# SCH_EasyEDA_EDA.net
KiCad netlist of a schematic drawn in EasyEDA
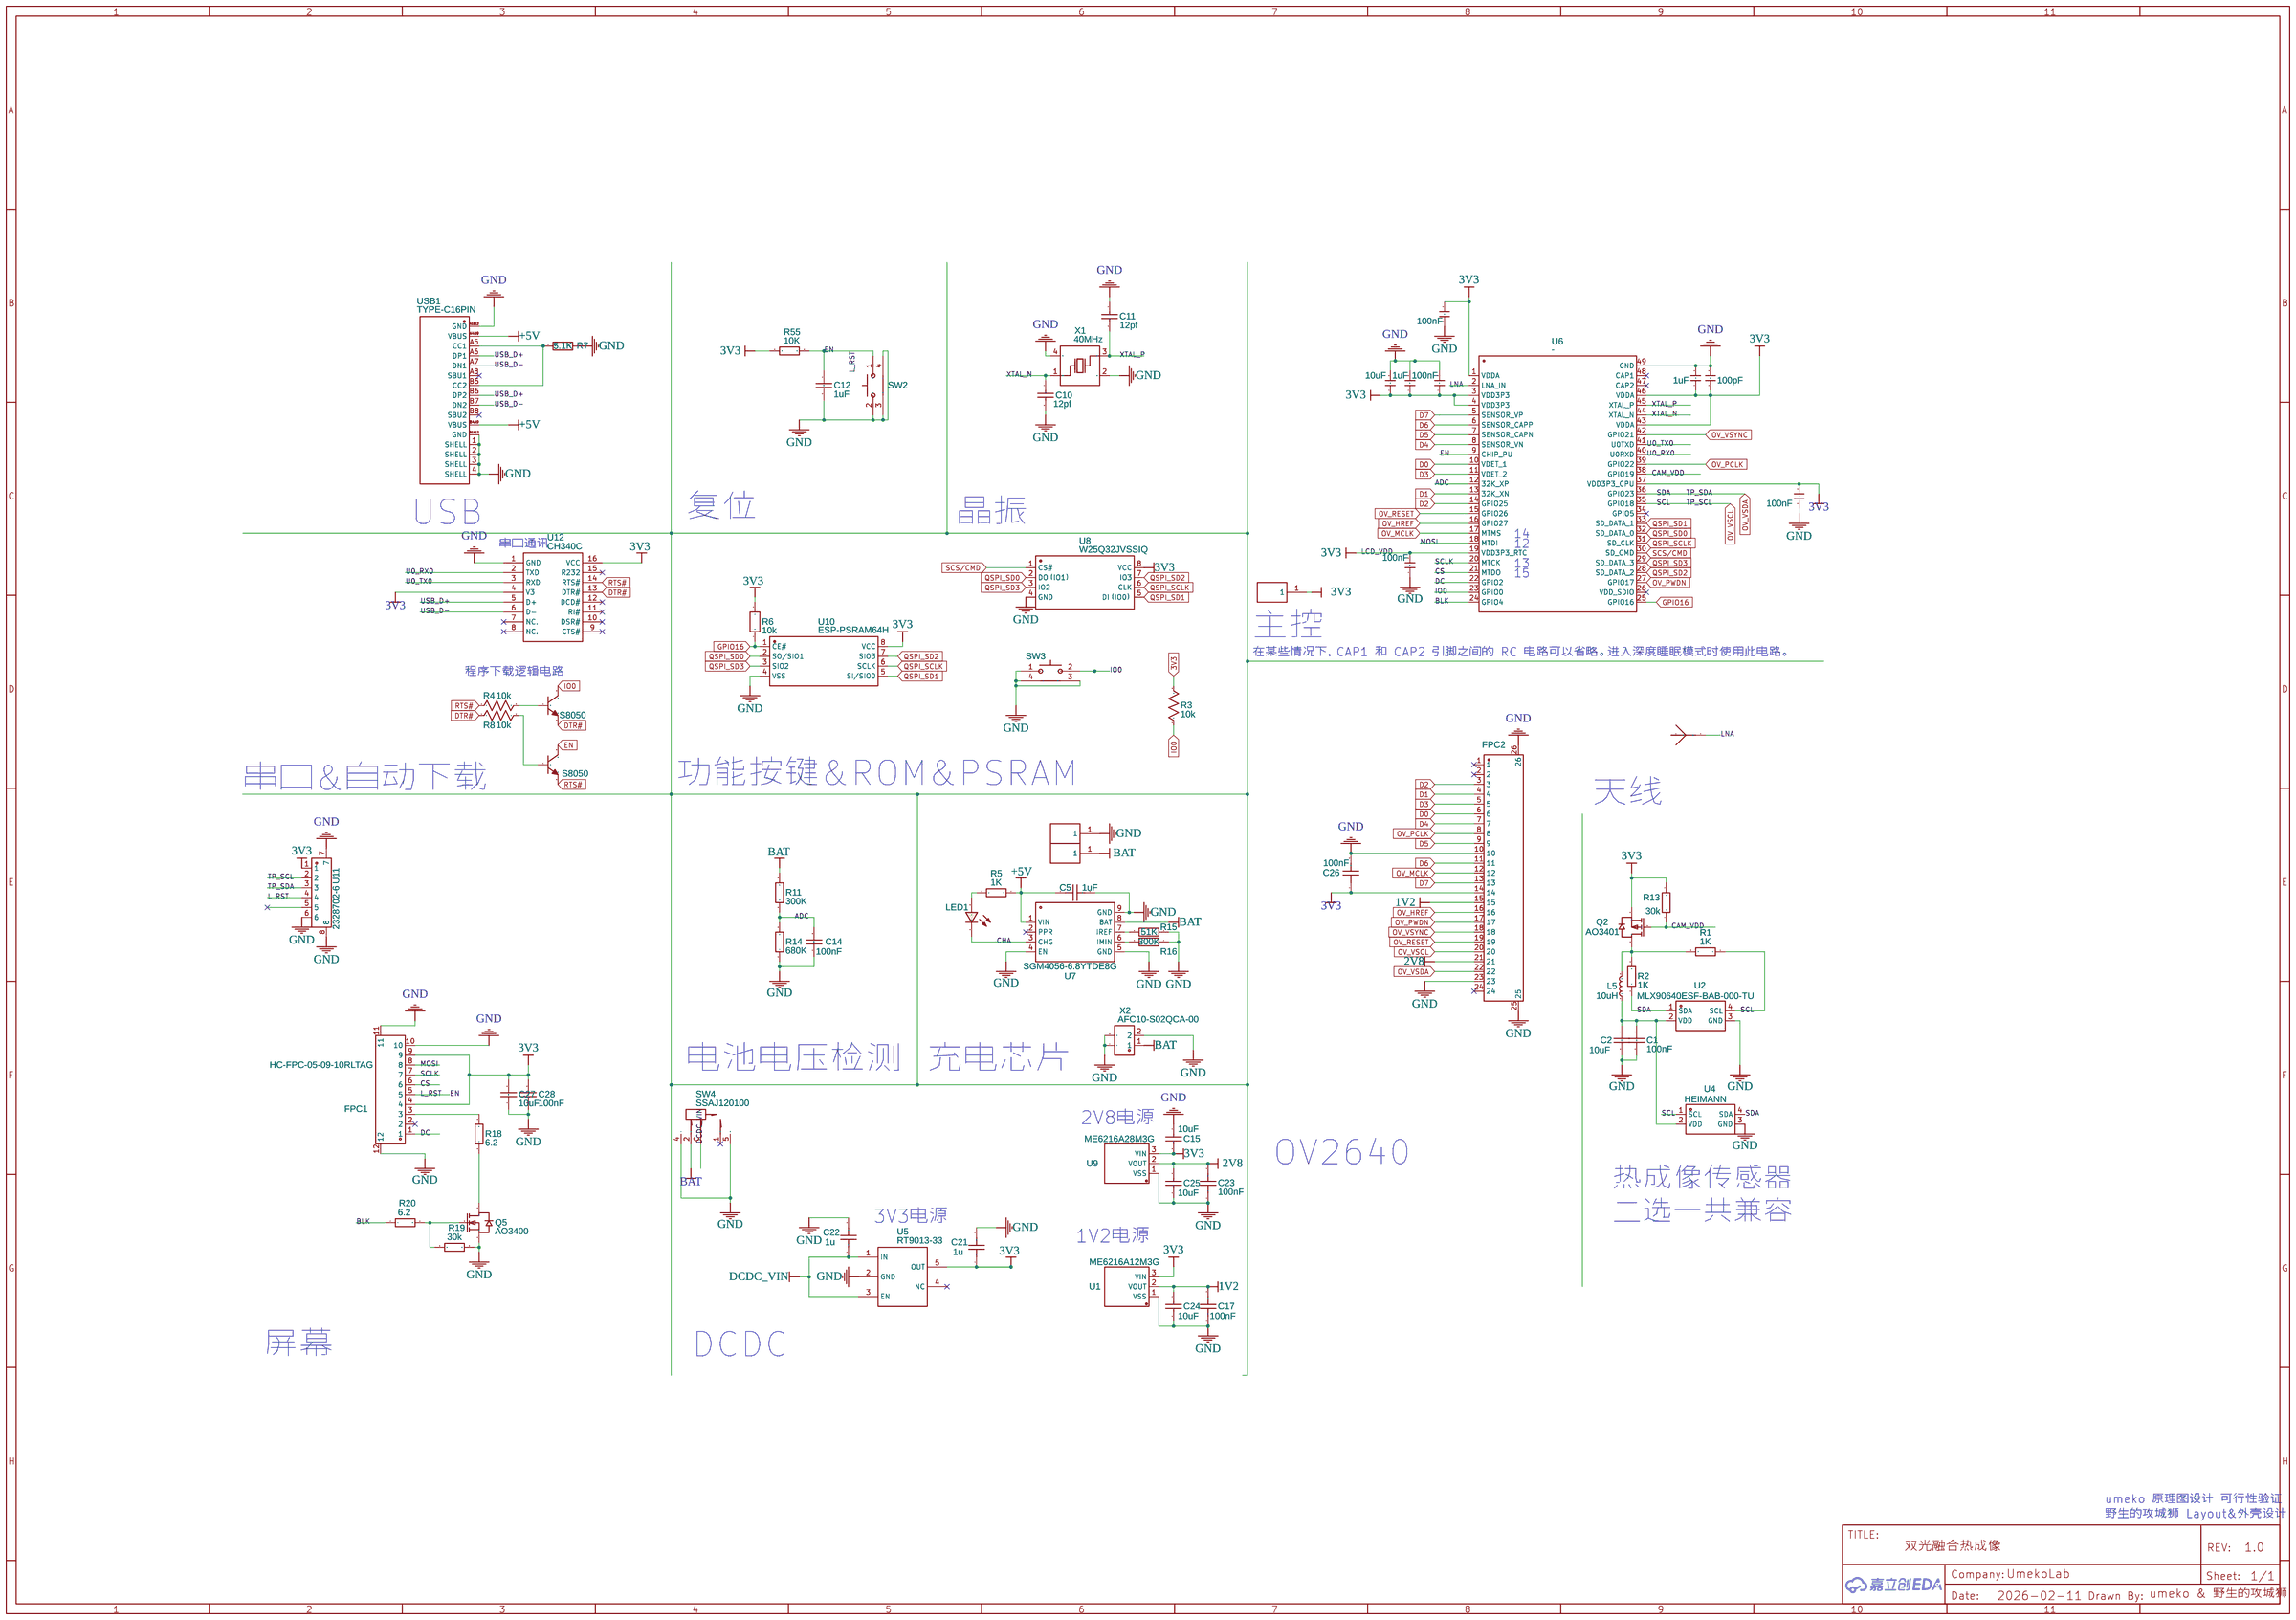
[diagram p0: schematic sheet]

(export (version "E")
  (design (tool "Eeschema 10.0.6"))
  (components
    (comp (ref "C1") (value "100nF") (libsource (lib "") (part "cap 0603_3")))
    (comp (ref "C2") (value "10uF") (libsource (lib "") (part "cap 0603")))
    (comp (ref "C5") (value "1uF") (libsource (lib "") (part "cap 0603_4")))
    (comp (ref "C6") (value "1uF") (libsource (lib "") (part "cap 0603_1")))
    (comp (ref "C7") (value "10uF") (libsource (lib "") (part "cap 0603_2")))
    (comp (ref "C8") (value "100nF") (libsource (lib "") (part "cap 0603_1")))
    (comp (ref "C10") (value "12pf") (libsource (lib "") (part "cap 0402_1")))
    (comp (ref "C11") (value "12pf") (libsource (lib "") (part "cap 0402")))
    (comp (ref "C12") (value "1uF") (libsource (lib "") (part "cap 0603")))
    (comp (ref "C13") (value "100nF") (libsource (lib "") (part "cap 0603_1")))
    (comp (ref "C14") (value "100nF") (libsource (lib "") (part "cap 0603")))
    (comp (ref "C15")
      (value "10uF")
      (fields (field (name "Manufacturer Part") "CL05A106MQ5NUNC") (field (name "Manufacturer") "SAMSUNG"))
      (libsource (lib "") (part "CL05A106MQ5NUNC"))
    )
    (comp (ref "C16") (value "1uF") (libsource (lib "") (part "cap 0603_1")))
    (comp (ref "C17")
      (value "100nF")
      (fields
        (field (name "Manufacturer Part") "CL05B104KB54PNC")
        (field (name "Manufacturer") "Samsung Electro-Mechanics")
      )
      (libsource (lib "") (part "CL05B104KB54PNC"))
    )
    (comp (ref "C18") (value "100pF") (libsource (lib "") (part "cap 0603_1")))
    (comp (ref "C19") (value "100nF") (libsource (lib "") (part "cap 0603_1")))
    (comp (ref "C20") (value "100nF") (libsource (lib "") (part "cap 0603_1")))
    (comp (ref "C21") (value "1u") (libsource (lib "") (part "C_0603_US")))
    (comp (ref "C22") (value "1u") (libsource (lib "") (part "C_0603_US")))
    (comp (ref "C23")
      (value "100nF")
      (fields
        (field (name "Manufacturer Part") "CL05B104KB54PNC")
        (field (name "Manufacturer") "Samsung Electro-Mechanics")
      )
      (libsource (lib "") (part "CL05B104KB54PNC"))
    )
    (comp (ref "C24")
      (value "10uF")
      (fields (field (name "Manufacturer Part") "CL05A106MQ5NUNC") (field (name "Manufacturer") "SAMSUNG"))
      (libsource (lib "") (part "CL05A106MQ5NUNC"))
    )
    (comp (ref "C25")
      (value "10uF")
      (fields (field (name "Manufacturer Part") "CL05A106MQ5NUNC") (field (name "Manufacturer") "SAMSUNG"))
      (libsource (lib "") (part "CL05A106MQ5NUNC"))
    )
    (comp (ref "C26")
      (value "100nF")
      (fields
        (field (name "Manufacturer Part") "CL05B104KB54PNC")
        (field (name "Manufacturer") "Samsung Electro-Mechanics")
      )
      (libsource (lib "") (part "CL05B104KB54PNC"))
    )
    (comp (ref "C27") (value "10uF") (libsource (lib "") (part "cap 0603")))
    (comp (ref "C28") (value "100nF") (libsource (lib "") (part "cap 0603")))
    (comp (ref "FPC1")
      (value "HC-FPC-05-09-10RLTAG")
      (fields (field (name "Manufacturer") "HCTL(华灿天禄)"))
      (libsource (lib "") (part "HC-FPC-05-09-10RLTAG"))
    )
    (comp (ref "FPC2")
      (value "AFC24-S24FIA-00")
      (fields (field (name "Manufacturer") "JUSHUO"))
      (libsource (lib "") (part "AFC24-S24FIA-00"))
    )
    (comp (ref "H1") (value "hp") (libsource (lib "") (part "hp")))
    (comp (ref "H2") (value "hp") (libsource (lib "") (part "hp")))
    (comp (ref "H3") (value "hp") (libsource (lib "") (part "hp")))
    (comp (ref "L2")
      (value "ANT-PCB-2.4G-IFA-AN043-TI-ORIGIN-X")
      (fields (field (name "Manufacturer") "GT"))
      (libsource (lib "") (part "ANT-PCB-2.4G-IFA-AN043-TI-ORIGIN-X"))
    )
    (comp (ref "L5") (value "10uH") (libsource (lib "") (part "0805-L")))
    (comp (ref "LED1") (value "led-0603") (libsource (lib "") (part "led-0603")))
    (comp (ref "Q1")
      (value "S8050")
      (fields (field (name "Manufacturer") "FUXINSEMI"))
      (libsource (lib "") (part "S8050_C908252"))
    )
    (comp (ref "Q2")
      (value "AO3401")
      (fields (field (name "Manufacturer") "IDCHIP(英锐芯)"))
      (libsource (lib "") (part "AO3401_C2848197"))
    )
    (comp (ref "Q4")
      (value "S8050")
      (fields (field (name "Manufacturer") "FUXINSEMI"))
      (libsource (lib "") (part "S8050_C908252"))
    )
    (comp (ref "Q5")
      (value "AO3400")
      (fields (field (name "Manufacturer") "IDCHIP(英锐芯)"))
      (libsource (lib "") (part "AO3400_C2848198"))
    )
    (comp (ref "R1") (value "1K") (libsource (lib "") (part "res-0603_2")))
    (comp (ref "R2") (value "1K") (libsource (lib "") (part "res-0603_1")))
    (comp (ref "R3") (value "10k") (libsource (lib "") (part "R_0603_US")))
    (comp (ref "R4") (value "10k") (libsource (lib "") (part "R_0603_US_1")))
    (comp (ref "R5") (value "1K") (libsource (lib "") (part "res-0603_2")))
    (comp (ref "R6") (value "10k") (libsource (lib "") (part "R_0603_EU")))
    (comp (ref "R7") (value "5.1K") (libsource (lib "") (part "res-0603_2")))
    (comp (ref "R8") (value "10k") (libsource (lib "") (part "R_0603_US_1")))
    (comp (ref "R11") (value "300K") (libsource (lib "") (part "res-0603_1")))
    (comp (ref "R13") (value "30k") (libsource (lib "") (part "res-0603_1")))
    (comp (ref "R14") (value "680K") (libsource (lib "") (part "res-0603_1")))
    (comp (ref "R15") (value "51K") (libsource (lib "") (part "res-0603_2")))
    (comp (ref "R16") (value "300K") (libsource (lib "") (part "res-0603_2")))
    (comp (ref "R18") (value "6.2") (libsource (lib "") (part "res-0603_1")))
    (comp (ref "R19") (value "30k") (libsource (lib "") (part "res-0603")))
    (comp (ref "R20") (value "6.2") (libsource (lib "") (part "res-0603")))
    (comp (ref "R55") (value "10K") (libsource (lib "") (part "res-0603")))
    (comp (ref "SW2") (value "1TS003B") (libsource (lib "") (part "1TS003B-1900-3500A")))
    (comp (ref "SW3") (value "1TS003B") (libsource (lib "") (part "1TS003B-1900-3500A_1")))
    (comp (ref "SW4")
      (value "SSAJ120100")
      (fields (field (name "Manufacturer") "ALPSALPINE(阿尔卑斯阿尔派)"))
      (libsource (lib "") (part "SSAJ120100"))
    )
    (comp (ref "U1")
      (value "ME6216A12M3G")
      (fields (field (name "Manufacturer") "Nanjing Micro One Elec"))
      (libsource (lib "") (part "ME6216A12M3G"))
    )
    (comp (ref "U2") (value "MLX90640ESF-BAB-000-TU") (libsource (lib "") (part "MLX90640ESF-BAB-000-TU")))
    (comp (ref "U4") (value "HEIMANN") (libsource (lib "") (part "MLX90640ESF-BAB-000-TU_1")))
    (comp (ref "U5")
      (value "RT9013-33")
      (fields (field (name "Manufacturer Part") "RT9013-33GB") (field (name "Manufacturer") "RICHTEK"))
      (libsource (lib "") (part "RT9013-33"))
    )
    (comp (ref "U6")
      (value "-")
      (fields (field (name "Manufacturer Part") "ESP32-D0WD") (field (name "Manufacturer") "ESPRESSIF(乐鑫)"))
      (libsource (lib "") (part "ESP32-D0WD"))
    )
    (comp (ref "U7") (value "SGM4056-6.8YTDE8G") (libsource (lib "") (part "SGM4056-6.8YTDE8G")))
    (comp (ref "U8")
      (value "W25Q32JVSSIQ")
      (fields (field (name "Manufacturer") "WINBOND"))
      (libsource (lib "") (part "W25Q32JVSSIQ"))
    )
    (comp (ref "U9")
      (value "ME6216A28M3G")
      (fields (field (name "Manufacturer") "Nanjing Micro One Elec"))
      (libsource (lib "") (part "ME6216A28M3G"))
    )
    (comp (ref "U10") (value "ESP-PSRAM64H") (libsource (lib "") (part "ESP-PSRAM64H")))
    (comp (ref "U11")
      (value "2328702-6")
      (fields (field (name "Manufacturer") "TE Connectivity(泰科电子)"))
      (libsource (lib "") (part "2328702-6"))
    )
    (comp (ref "U12")
      (value "CH340C")
      (fields (field (name "Manufacturer") "WCH"))
      (libsource (lib "") (part "CH340C"))
    )
    (comp (ref "USB1")
      (value "TYPE-C16PIN")
      (fields (field (name "Manufacturer") "SHOU HAN"))
      (libsource (lib "") (part "TYPE-C16PIN"))
    )
    (comp (ref "X1")
      (value "40MHz")
      (fields (field (name "Manufacturer Part") "X322540MPB4SI") (field (name "Manufacturer") "YXC(扬兴晶振)"))
      (libsource (lib "") (part "X322540MPB4SI"))
    )
    (comp (ref "X2")
      (value "AFC10-S02QCA-00")
      (fields (field (name "Manufacturer") "JS(钜硕电子)"))
      (libsource (lib "") (part "AFC10-S02QCA-00"))
    )
  )
  (nets
    (net (code "1") (name "+5V") (class "Default")
      (node (ref "C5") (pin "1") (pinfunction "1_1") (pintype "unspecified"))
      (node (ref "R5") (pin "1") (pinfunction "1_1") (pintype "unspecified"))
      (node (ref "U7") (pin "1") (pinfunction "VIN_1") (pintype "unspecified"))
      (node (ref "USB1") (pin "A4B9") (pinfunction "VBUS_A4B9") (pintype "unspecified"))
      (node (ref "USB1") (pin "B4A9") (pinfunction "VBUS_B4A9") (pintype "unspecified"))
    )
    (net (code "2") (name "/ADC") (class "Default")
      (node (ref "C14") (pin "1") (pinfunction "1_1") (pintype "unspecified"))
      (node (ref "R11") (pin "1") (pinfunction "1_1") (pintype "unspecified"))
      (node (ref "R14") (pin "2") (pinfunction "2_2") (pintype "unspecified"))
      (node (ref "U6") (pin "12") (pinfunction "32K_XP_12") (pintype "unspecified"))
    )
    (net (code "3") (name "/BLK") (class "Default")
      (node (ref "R20") (pin "1") (pinfunction "1_1") (pintype "unspecified"))
      (node (ref "U6") (pin "24") (pinfunction "GPIO4_24") (pintype "unspecified"))
    )
    (net (code "4") (name "/CAM_VDD") (class "Default")
      (node (ref "Q2") (pin "1") (pinfunction "G_1") (pintype "unspecified"))
      (node (ref "R13") (pin "1") (pinfunction "1_1") (pintype "unspecified"))
      (node (ref "U6") (pin "38") (pinfunction "GPIO19_38") (pintype "unspecified"))
    )
    (net (code "5") (name "/CHA") (class "Default")
      (node (ref "LED1") (pin "1") (pinfunction "C_1") (pintype "input"))
      (node (ref "U7") (pin "3") (pinfunction "CHG_3") (pintype "unspecified"))
    )
    (net (code "6") (name "/CS") (class "Default")
      (node (ref "FPC1") (pin "6") (pinfunction "6_6") (pintype "unspecified"))
      (node (ref "U6") (pin "21") (pinfunction "MTDO_21") (pintype "unspecified"))
    )
    (net (code "7") (name "/DC") (class "Default")
      (node (ref "FPC1") (pin "1") (pinfunction "1_1") (pintype "unspecified"))
      (node (ref "U6") (pin "22") (pinfunction "GPIO2_22") (pintype "unspecified"))
    )
    (net (code "8") (name "/LNA") (class "Default")
      (node (ref "L2") (pin "4") (pinfunction "R4-2_4") (pintype "unspecified"))
      (node (ref "U6") (pin "2") (pinfunction "LNA_IN_2") (pintype "unspecified"))
    )
    (net (code "9") (name "/MOSI") (class "Default")
      (node (ref "FPC1") (pin "8") (pinfunction "8_8") (pintype "unspecified"))
      (node (ref "U6") (pin "18") (pinfunction "MTDI_18") (pintype "unspecified"))
    )
    (net (code "10") (name "/SCLK") (class "Default")
      (node (ref "FPC1") (pin "7") (pinfunction "7_7") (pintype "unspecified"))
      (node (ref "U6") (pin "20") (pinfunction "MTCK_20") (pintype "unspecified"))
    )
    (net (code "11") (name "/U0_RX0") (class "Default")
      (node (ref "U12") (pin "2") (pinfunction "TXD_2") (pintype "unspecified"))
      (node (ref "U6") (pin "40") (pinfunction "U0RXD_40") (pintype "unspecified"))
    )
    (net (code "12") (name "/U0_TX0") (class "Default")
      (node (ref "U12") (pin "3") (pinfunction "RXD_3") (pintype "unspecified"))
      (node (ref "U6") (pin "41") (pinfunction "U0TXD_41") (pintype "unspecified"))
    )
    (net (code "13") (name "/USB_D+") (class "Default")
      (node (ref "U12") (pin "5") (pinfunction "D+_5") (pintype "unspecified"))
      (node (ref "USB1") (pin "A6") (pinfunction "DP1_A6") (pintype "unspecified"))
      (node (ref "USB1") (pin "B6") (pinfunction "DP2_B6") (pintype "unspecified"))
    )
    (net (code "14") (name "/USB_D-") (class "Default")
      (node (ref "U12") (pin "6") (pinfunction "D-_6") (pintype "unspecified"))
      (node (ref "USB1") (pin "A7") (pinfunction "DN1_A7") (pintype "unspecified"))
      (node (ref "USB1") (pin "B7") (pinfunction "DN2_B7") (pintype "unspecified"))
    )
    (net (code "15") (name "/XTAL_N") (class "Default")
      (node (ref "C10") (pin "1") (pinfunction "1_1") (pintype "input"))
      (node (ref "U6") (pin "44") (pinfunction "XTAL_N_44") (pintype "unspecified"))
      (node (ref "X1") (pin "1") (pinfunction "OSC1_1") (pintype "unspecified"))
    )
    (net (code "16") (name "/XTAL_P") (class "Default")
      (node (ref "C11") (pin "2") (pinfunction "2_2") (pintype "input"))
      (node (ref "U6") (pin "45") (pinfunction "XTAL_P_45") (pintype "unspecified"))
      (node (ref "X1") (pin "3") (pinfunction "OSC2_3") (pintype "unspecified"))
    )
    (net (code "17") (name "1V2") (class "Default")
      (node (ref "C17") (pin "2") (pinfunction "2_2") (pintype "unspecified"))
      (node (ref "C24") (pin "1") (pinfunction "1_1") (pintype "input"))
      (node (ref "FPC2") (pin "15") (pinfunction "15_15") (pintype "unspecified"))
      (node (ref "U1") (pin "2") (pinfunction "VOUT_2") (pintype "unspecified"))
    )
    (net (code "18") (name "2V8") (class "Default")
      (node (ref "C23") (pin "2") (pinfunction "2_2") (pintype "unspecified"))
      (node (ref "C25") (pin "1") (pinfunction "1_1") (pintype "input"))
      (node (ref "FPC2") (pin "21") (pinfunction "21_21") (pintype "unspecified"))
      (node (ref "U9") (pin "2") (pinfunction "VOUT_2") (pintype "unspecified"))
    )
    (net (code "19") (name "3V3") (class "Default")
      (node (ref "C13") (pin "2") (pinfunction "2_2") (pintype "unspecified"))
      (node (ref "C15") (pin "2") (pinfunction "2_2") (pintype "input"))
      (node (ref "C16") (pin "1") (pinfunction "1_1") (pintype "unspecified"))
      (node (ref "C18") (pin "1") (pinfunction "1_1") (pintype "unspecified"))
      (node (ref "C19") (pin "2") (pinfunction "2_2") (pintype "unspecified"))
      (node (ref "C20") (pin "2") (pinfunction "2_2") (pintype "unspecified"))
      (node (ref "C21") (pin "1") (pinfunction "1_1") (pintype "unspecified"))
      (node (ref "C26") (pin "1") (pinfunction "1_1") (pintype "unspecified"))
      (node (ref "C27") (pin "1") (pinfunction "1_1") (pintype "unspecified"))
      (node (ref "C28") (pin "1") (pinfunction "1_1") (pintype "unspecified"))
      (node (ref "C6") (pin "1") (pinfunction "1_1") (pintype "unspecified"))
      (node (ref "C7") (pin "1") (pinfunction "1_1") (pintype "unspecified"))
      (node (ref "C8") (pin "1") (pinfunction "1_1") (pintype "unspecified"))
      (node (ref "FPC1") (pin "4") (pinfunction "4_4") (pintype "unspecified"))
      (node (ref "FPC1") (pin "9") (pinfunction "9_9") (pintype "unspecified"))
      (node (ref "FPC2") (pin "14") (pinfunction "14_14") (pintype "unspecified"))
      (node (ref "H3") (pin "1") (pinfunction "1_1") (pintype "unspecified"))
      (node (ref "Q2") (pin "2") (pinfunction "S_2") (pintype "unspecified"))
      (node (ref "R13") (pin "2") (pinfunction "2_2") (pintype "unspecified"))
      (node (ref "R3") (pin "2") (pinfunction "2_2") (pintype "unspecified"))
      (node (ref "R55") (pin "1") (pinfunction "1_1") (pintype "unspecified"))
      (node (ref "R6") (pin "2") (pinfunction "2_2") (pintype "unspecified"))
      (node (ref "U1") (pin "3") (pinfunction "VIN_3") (pintype "unspecified"))
      (node (ref "U10") (pin "8") (pinfunction "VCC_8") (pintype "unspecified"))
      (node (ref "U11") (pin "1") (pinfunction "1_1") (pintype "unspecified"))
      (node (ref "U12") (pin "16") (pinfunction "VCC_16") (pintype "unspecified"))
      (node (ref "U12") (pin "4") (pinfunction "V3_4") (pintype "unspecified"))
      (node (ref "U5") (pin "5") (pinfunction "OUT_5") (pintype "unspecified"))
      (node (ref "U6") (pin "1") (pinfunction "VDDA_1") (pintype "unspecified"))
      (node (ref "U6") (pin "19") (pinfunction "VDD3P3_RTC_19") (pintype "unspecified"))
      (node (ref "U6") (pin "3") (pinfunction "VDD3P3_3") (pintype "unspecified"))
      (node (ref "U6") (pin "37") (pinfunction "VDD3P3_CPU_37") (pintype "unspecified"))
      (node (ref "U6") (pin "4") (pinfunction "VDD3P3_4") (pintype "unspecified"))
      (node (ref "U6") (pin "43") (pinfunction "VDDA_43") (pintype "unspecified"))
      (node (ref "U6") (pin "46") (pinfunction "VDDA_46") (pintype "unspecified"))
      (node (ref "U8") (pin "8") (pinfunction "VCC_8") (pintype "unspecified"))
      (node (ref "U9") (pin "3") (pinfunction "VIN_3") (pintype "unspecified"))
    )
    (net (code "20") (name "BAT") (class "Default")
      (node (ref "H2") (pin "1") (pinfunction "1_1") (pintype "unspecified"))
      (node (ref "R11") (pin "2") (pinfunction "2_2") (pintype "unspecified"))
      (node (ref "SW4") (pin "2") (pinfunction "2_2") (pintype "unspecified"))
      (node (ref "U7") (pin "8") (pinfunction "BAT_8") (pintype "unspecified"))
      (node (ref "X2") (pin "1") (pinfunction "1_1") (pintype "unspecified"))
    )
    (net (code "21") (name "D0") (class "Default")
      (node (ref "FPC2") (pin "6") (pinfunction "6_6") (pintype "unspecified"))
      (node (ref "U6") (pin "10") (pinfunction "VDET_1_10") (pintype "unspecified"))
    )
    (net (code "22") (name "D1") (class "Default")
      (node (ref "FPC2") (pin "4") (pinfunction "4_4") (pintype "unspecified"))
      (node (ref "U6") (pin "13") (pinfunction "32K_XN_13") (pintype "unspecified"))
    )
    (net (code "23") (name "D2") (class "Default")
      (node (ref "FPC2") (pin "3") (pinfunction "3_3") (pintype "unspecified"))
      (node (ref "U6") (pin "14") (pinfunction "GPIO25_14") (pintype "unspecified"))
    )
    (net (code "24") (name "D3") (class "Default")
      (node (ref "FPC2") (pin "5") (pinfunction "5_5") (pintype "unspecified"))
      (node (ref "U6") (pin "11") (pinfunction "VDET_2_11") (pintype "unspecified"))
    )
    (net (code "25") (name "D4") (class "Default")
      (node (ref "FPC2") (pin "7") (pinfunction "7_7") (pintype "unspecified"))
      (node (ref "U6") (pin "8") (pinfunction "SENSOR_VN_8") (pintype "unspecified"))
    )
    (net (code "26") (name "D5") (class "Default")
      (node (ref "FPC2") (pin "9") (pinfunction "9_9") (pintype "unspecified"))
      (node (ref "U6") (pin "7") (pinfunction "SENSOR_CAPN_7") (pintype "unspecified"))
    )
    (net (code "27") (name "D6") (class "Default")
      (node (ref "FPC2") (pin "11") (pinfunction "11_11") (pintype "unspecified"))
      (node (ref "U6") (pin "6") (pinfunction "SENSOR_CAPP_6") (pintype "unspecified"))
    )
    (net (code "28") (name "D7") (class "Default")
      (node (ref "FPC2") (pin "13") (pinfunction "13_13") (pintype "unspecified"))
      (node (ref "U6") (pin "5") (pinfunction "SENSOR_VP_5") (pintype "unspecified"))
    )
    (net (code "29") (name "DCDC_VIN") (class "Default")
      (node (ref "C22") (pin "1") (pinfunction "1_1") (pintype "unspecified"))
      (node (ref "SW4") (pin "C") (pinfunction "C_C") (pintype "unspecified"))
      (node (ref "U5") (pin "1") (pinfunction "IN_1") (pintype "unspecified"))
      (node (ref "U5") (pin "3") (pinfunction "EN_3") (pintype "unspecified"))
    )
    (net (code "30") (name "DTR#") (class "Default")
      (node (ref "Q4") (pin "2") (pinfunction "E_2") (pintype "input"))
      (node (ref "R8") (pin "1") (pinfunction "1_1") (pintype "unspecified"))
      (node (ref "U12") (pin "13") (pinfunction "DTR#_13") (pintype "unspecified"))
    )
    (net (code "31") (name "EN") (class "Default")
      (node (ref "C12") (pin "1") (pinfunction "1_1") (pintype "unspecified"))
      (node (ref "FPC1") (pin "5") (pinfunction "5_5") (pintype "unspecified"))
      (node (ref "Q1") (pin "3") (pinfunction "C_3") (pintype "input"))
      (node (ref "R55") (pin "2") (pinfunction "2_2") (pintype "unspecified"))
      (node (ref "SW2") (pin "1") (pinfunction "1_1") (pintype "unspecified"))
      (node (ref "U11") (pin "4") (pinfunction "4_4") (pintype "unspecified"))
      (node (ref "U6") (pin "9") (pinfunction "CHIP_PU_9") (pintype "unspecified"))
    )
    (net (code "32") (name "GND") (class "Default")
      (node (ref "C1") (pin "2") (pinfunction "2_2") (pintype "unspecified"))
      (node (ref "C10") (pin "2") (pinfunction "2_2") (pintype "input"))
      (node (ref "C11") (pin "1") (pinfunction "1_1") (pintype "input"))
      (node (ref "C12") (pin "2") (pinfunction "2_2") (pintype "unspecified"))
      (node (ref "C13") (pin "1") (pinfunction "1_1") (pintype "unspecified"))
      (node (ref "C14") (pin "2") (pinfunction "2_2") (pintype "unspecified"))
      (node (ref "C15") (pin "1") (pinfunction "1_1") (pintype "input"))
      (node (ref "C16") (pin "2") (pinfunction "2_2") (pintype "unspecified"))
      (node (ref "C17") (pin "1") (pinfunction "1_1") (pintype "unspecified"))
      (node (ref "C18") (pin "2") (pinfunction "2_2") (pintype "unspecified"))
      (node (ref "C19") (pin "1") (pinfunction "1_1") (pintype "unspecified"))
      (node (ref "C2") (pin "2") (pinfunction "2_2") (pintype "unspecified"))
      (node (ref "C20") (pin "1") (pinfunction "1_1") (pintype "unspecified"))
      (node (ref "C21") (pin "2") (pinfunction "2_2") (pintype "unspecified"))
      (node (ref "C22") (pin "2") (pinfunction "2_2") (pintype "unspecified"))
      (node (ref "C23") (pin "1") (pinfunction "1_1") (pintype "unspecified"))
      (node (ref "C24") (pin "2") (pinfunction "2_2") (pintype "input"))
      (node (ref "C25") (pin "2") (pinfunction "2_2") (pintype "input"))
      (node (ref "C26") (pin "2") (pinfunction "2_2") (pintype "unspecified"))
      (node (ref "C27") (pin "2") (pinfunction "2_2") (pintype "unspecified"))
      (node (ref "C28") (pin "2") (pinfunction "2_2") (pintype "unspecified"))
      (node (ref "C5") (pin "2") (pinfunction "2_2") (pintype "unspecified"))
      (node (ref "C6") (pin "2") (pinfunction "2_2") (pintype "unspecified"))
      (node (ref "C7") (pin "2") (pinfunction "2_2") (pintype "unspecified"))
      (node (ref "C8") (pin "2") (pinfunction "2_2") (pintype "unspecified"))
      (node (ref "FPC1") (pin "10") (pinfunction "10_10") (pintype "unspecified"))
      (node (ref "FPC1") (pin "11") (pinfunction "11_11") (pintype "unspecified"))
      (node (ref "FPC1") (pin "12") (pinfunction "12_12") (pintype "unspecified"))
      (node (ref "FPC2") (pin "10") (pinfunction "10_10") (pintype "unspecified"))
      (node (ref "FPC2") (pin "23") (pinfunction "23_23") (pintype "unspecified"))
      (node (ref "FPC2") (pin "25") (pinfunction "25_25") (pintype "unspecified"))
      (node (ref "FPC2") (pin "26") (pinfunction "26_26") (pintype "unspecified"))
      (node (ref "H1") (pin "1") (pinfunction "1_1") (pintype "unspecified"))
      (node (ref "Q5") (pin "2") (pinfunction "S_2") (pintype "unspecified"))
      (node (ref "R14") (pin "1") (pinfunction "1_1") (pintype "unspecified"))
      (node (ref "R15") (pin "1") (pinfunction "1_1") (pintype "unspecified"))
      (node (ref "R16") (pin "1") (pinfunction "1_1") (pintype "unspecified"))
      (node (ref "R19") (pin "2") (pinfunction "2_2") (pintype "unspecified"))
      (node (ref "R7") (pin "1") (pinfunction "1_1") (pintype "unspecified"))
      (node (ref "SW2") (pin "2") (pinfunction "2_2") (pintype "unspecified"))
      (node (ref "SW2") (pin "3") (pinfunction "3_3") (pintype "unspecified"))
      (node (ref "SW2") (pin "4") (pinfunction "4_4") (pintype "unspecified"))
      (node (ref "SW3") (pin "1") (pinfunction "1_1") (pintype "unspecified"))
      (node (ref "SW3") (pin "3") (pinfunction "3_3") (pintype "unspecified"))
      (node (ref "SW3") (pin "4") (pinfunction "4_4") (pintype "unspecified"))
      (node (ref "SW4") (pin "4") (pinfunction "4_4") (pintype "unspecified"))
      (node (ref "SW4") (pin "5") (pinfunction "5_5") (pintype "unspecified"))
      (node (ref "U1") (pin "1") (pinfunction "VSS_1") (pintype "unspecified"))
      (node (ref "U10") (pin "4") (pinfunction "VSS_4") (pintype "unspecified"))
      (node (ref "U11") (pin "6") (pinfunction "6_6") (pintype "unspecified"))
      (node (ref "U11") (pin "7") (pinfunction "7_7") (pintype "unspecified"))
      (node (ref "U11") (pin "8") (pinfunction "8_8") (pintype "unspecified"))
      (node (ref "U12") (pin "1") (pinfunction "GND_1") (pintype "unspecified"))
      (node (ref "U2") (pin "3") (pinfunction "GND_3") (pintype "unspecified"))
      (node (ref "U4") (pin "3") (pinfunction "GND_3") (pintype "unspecified"))
      (node (ref "U5") (pin "2") (pinfunction "GND_2") (pintype "unspecified"))
      (node (ref "U6") (pin "49") (pinfunction "GND_49") (pintype "unspecified"))
      (node (ref "U7") (pin "4") (pinfunction "EN_4") (pintype "unspecified"))
      (node (ref "U7") (pin "5") (pinfunction "GND_5") (pintype "unspecified"))
      (node (ref "U7") (pin "9") (pinfunction "GND_9") (pintype "unspecified"))
      (node (ref "U8") (pin "4") (pinfunction "GND_4") (pintype "unspecified"))
      (node (ref "U9") (pin "1") (pinfunction "VSS_1") (pintype "unspecified"))
      (node (ref "USB1") (pin "1") (pinfunction "SHELL_1") (pintype "unspecified"))
      (node (ref "USB1") (pin "2") (pinfunction "SHELL_2") (pintype "unspecified"))
      (node (ref "USB1") (pin "3") (pinfunction "SHELL_3") (pintype "unspecified"))
      (node (ref "USB1") (pin "4") (pinfunction "SHELL_4") (pintype "unspecified"))
      (node (ref "USB1") (pin "A1B12") (pinfunction "GND_A1B12") (pintype "unspecified"))
      (node (ref "USB1") (pin "B1A12") (pinfunction "GND_B1A12") (pintype "unspecified"))
      (node (ref "X1") (pin "2") (pinfunction "GND_2") (pintype "unspecified"))
      (node (ref "X1") (pin "4") (pinfunction "GND_4") (pintype "unspecified"))
      (node (ref "X2") (pin "2") (pinfunction "2_2") (pintype "unspecified"))
      (node (ref "X2") (pin "3") (pinfunction "3_3") (pintype "unspecified"))
      (node (ref "X2") (pin "4") (pinfunction "4_4") (pintype "unspecified"))
    )
    (net (code "33") (name "GPIO16") (class "Default")
      (node (ref "R6") (pin "1") (pinfunction "1_1") (pintype "unspecified"))
      (node (ref "U10") (pin "1") (pinfunction "CE#_1") (pintype "unspecified"))
      (node (ref "U6") (pin "25") (pinfunction "GPIO16_25") (pintype "unspecified"))
    )
    (net (code "34") (name "IO0") (class "Default")
      (node (ref "Q4") (pin "3") (pinfunction "C_3") (pintype "input"))
      (node (ref "R3") (pin "1") (pinfunction "1_1") (pintype "unspecified"))
      (node (ref "SW3") (pin "2") (pinfunction "2_2") (pintype "unspecified"))
      (node (ref "U6") (pin "23") (pinfunction "GPIO0_23") (pintype "unspecified"))
    )
    (net (code "35") (name "Net-(FPC1-Pad3)") (class "Default")
      (node (ref "FPC1") (pin "3") (pinfunction "3_3") (pintype "unspecified"))
      (node (ref "R18") (pin "2") (pinfunction "2_2") (pintype "unspecified"))
    )
    (net (code "36") (name "Net-(LED1-A)") (class "Default")
      (node (ref "LED1") (pin "2") (pinfunction "A_2") (pintype "input"))
      (node (ref "R5") (pin "2") (pinfunction "2_2") (pintype "unspecified"))
    )
    (net (code "37") (name "Net-(Q1-B)") (class "Default")
      (node (ref "Q1") (pin "1") (pinfunction "B_1") (pintype "input"))
      (node (ref "R8") (pin "2") (pinfunction "2_2") (pintype "unspecified"))
    )
    (net (code "38") (name "Net-(Q2-D)") (class "Default")
      (node (ref "L5") (pin "2") (pinfunction "2_2") (pintype "unspecified"))
      (node (ref "Q2") (pin "3") (pinfunction "D_3") (pintype "unspecified"))
      (node (ref "R1") (pin "2") (pinfunction "2_2") (pintype "unspecified"))
      (node (ref "R2") (pin "2") (pinfunction "2_2") (pintype "unspecified"))
    )
    (net (code "39") (name "Net-(Q4-B)") (class "Default")
      (node (ref "Q4") (pin "1") (pinfunction "B_1") (pintype "input"))
      (node (ref "R4") (pin "2") (pinfunction "2_2") (pintype "unspecified"))
    )
    (net (code "40") (name "Net-(Q5-D)") (class "Default")
      (node (ref "Q5") (pin "3") (pinfunction "D_3") (pintype "unspecified"))
      (node (ref "R18") (pin "1") (pinfunction "1_1") (pintype "unspecified"))
    )
    (net (code "41") (name "Net-(Q5-G)") (class "Default")
      (node (ref "Q5") (pin "1") (pinfunction "G_1") (pintype "unspecified"))
      (node (ref "R19") (pin "1") (pinfunction "1_1") (pintype "unspecified"))
      (node (ref "R20") (pin "2") (pinfunction "2_2") (pintype "unspecified"))
    )
    (net (code "42") (name "Net-(U2-VDD)") (class "Default")
      (node (ref "C1") (pin "1") (pinfunction "1_1") (pintype "unspecified"))
      (node (ref "C2") (pin "1") (pinfunction "1_1") (pintype "unspecified"))
      (node (ref "L5") (pin "1") (pinfunction "1_1") (pintype "unspecified"))
      (node (ref "U2") (pin "2") (pinfunction "VDD_2") (pintype "unspecified"))
      (node (ref "U4") (pin "2") (pinfunction "VDD_2") (pintype "unspecified"))
    )
    (net (code "43") (name "Net-(U7-IMIN)") (class "Default")
      (node (ref "R16") (pin "2") (pinfunction "2_2") (pintype "unspecified"))
      (node (ref "U7") (pin "6") (pinfunction "IMIN_6") (pintype "unspecified"))
    )
    (net (code "44") (name "Net-(U7-IREF)") (class "Default")
      (node (ref "R15") (pin "2") (pinfunction "2_2") (pintype "unspecified"))
      (node (ref "U7") (pin "7") (pinfunction "IREF_7") (pintype "unspecified"))
    )
    (net (code "45") (name "Net-(USB1-CC1)") (class "Default")
      (node (ref "R7") (pin "2") (pinfunction "2_2") (pintype "unspecified"))
      (node (ref "USB1") (pin "A5") (pinfunction "CC1_A5") (pintype "unspecified"))
      (node (ref "USB1") (pin "B5") (pinfunction "CC2_B5") (pintype "unspecified"))
    )
    (net (code "46") (name "OV_HREF") (class "Default")
      (node (ref "FPC2") (pin "16") (pinfunction "16_16") (pintype "unspecified"))
      (node (ref "U6") (pin "16") (pinfunction "GPIO27_16") (pintype "unspecified"))
    )
    (net (code "47") (name "OV_MCLK") (class "Default")
      (node (ref "FPC2") (pin "12") (pinfunction "12_12") (pintype "unspecified"))
      (node (ref "U6") (pin "17") (pinfunction "MTMS_17") (pintype "unspecified"))
    )
    (net (code "48") (name "OV_PCLK") (class "Default")
      (node (ref "FPC2") (pin "8") (pinfunction "8_8") (pintype "unspecified"))
      (node (ref "U6") (pin "39") (pinfunction "GPIO22_39") (pintype "unspecified"))
    )
    (net (code "49") (name "OV_PWDN") (class "Default")
      (node (ref "FPC2") (pin "17") (pinfunction "17_17") (pintype "unspecified"))
      (node (ref "U6") (pin "27") (pinfunction "GPIO17_27") (pintype "unspecified"))
    )
    (net (code "50") (name "OV_RESET") (class "Default")
      (node (ref "FPC2") (pin "19") (pinfunction "19_19") (pintype "unspecified"))
      (node (ref "U6") (pin "15") (pinfunction "GPIO26_15") (pintype "unspecified"))
    )
    (net (code "51") (name "OV_VSCL") (class "Default")
      (node (ref "FPC2") (pin "20") (pinfunction "20_20") (pintype "unspecified"))
      (node (ref "R1") (pin "1") (pinfunction "1_1") (pintype "unspecified"))
      (node (ref "U11") (pin "2") (pinfunction "2_2") (pintype "unspecified"))
      (node (ref "U2") (pin "4") (pinfunction "SCL_4") (pintype "unspecified"))
      (node (ref "U4") (pin "1") (pinfunction "SCL_1") (pintype "unspecified"))
      (node (ref "U6") (pin "35") (pinfunction "GPIO18_35") (pintype "unspecified"))
    )
    (net (code "52") (name "OV_VSDA") (class "Default")
      (node (ref "FPC2") (pin "22") (pinfunction "22_22") (pintype "unspecified"))
      (node (ref "R2") (pin "1") (pinfunction "1_1") (pintype "unspecified"))
      (node (ref "U11") (pin "3") (pinfunction "3_3") (pintype "unspecified"))
      (node (ref "U2") (pin "1") (pinfunction "SDA_1") (pintype "unspecified"))
      (node (ref "U4") (pin "4") (pinfunction "SDA_4") (pintype "unspecified"))
      (node (ref "U6") (pin "36") (pinfunction "GPIO23_36") (pintype "unspecified"))
    )
    (net (code "53") (name "OV_VSYNC") (class "Default")
      (node (ref "FPC2") (pin "18") (pinfunction "18_18") (pintype "unspecified"))
      (node (ref "U6") (pin "42") (pinfunction "GPIO21_42") (pintype "unspecified"))
    )
    (net (code "54") (name "QSPI_SCLK") (class "Default")
      (node (ref "U10") (pin "6") (pinfunction "SCLK_6") (pintype "unspecified"))
      (node (ref "U6") (pin "31") (pinfunction "SD_CLK_31") (pintype "unspecified"))
      (node (ref "U8") (pin "6") (pinfunction "CLK_6") (pintype "unspecified"))
    )
    (net (code "55") (name "QSPI_SD0") (class "Default")
      (node (ref "U10") (pin "2") (pinfunction "SO/SIO1_2") (pintype "unspecified"))
      (node (ref "U6") (pin "32") (pinfunction "SD_DATA_0_32") (pintype "unspecified"))
      (node (ref "U8") (pin "2") (pinfunction "DO（IO1）_2") (pintype "unspecified"))
    )
    (net (code "56") (name "QSPI_SD1") (class "Default")
      (node (ref "U10") (pin "5") (pinfunction "SI/SIO0_5") (pintype "unspecified"))
      (node (ref "U6") (pin "33") (pinfunction "SD_DATA_1_33") (pintype "unspecified"))
      (node (ref "U8") (pin "5") (pinfunction "DI（IO0）_5") (pintype "unspecified"))
    )
    (net (code "57") (name "QSPI_SD2") (class "Default")
      (node (ref "U10") (pin "7") (pinfunction "SIO3_7") (pintype "unspecified"))
      (node (ref "U6") (pin "28") (pinfunction "SD_DATA_2_28") (pintype "unspecified"))
      (node (ref "U8") (pin "7") (pinfunction "IO3_7") (pintype "unspecified"))
    )
    (net (code "58") (name "QSPI_SD3") (class "Default")
      (node (ref "U10") (pin "3") (pinfunction "SIO2_3") (pintype "unspecified"))
      (node (ref "U6") (pin "29") (pinfunction "SD_DATA_3_29") (pintype "unspecified"))
      (node (ref "U8") (pin "3") (pinfunction "IO2_3") (pintype "unspecified"))
    )
    (net (code "59") (name "RTS#") (class "Default")
      (node (ref "Q1") (pin "2") (pinfunction "E_2") (pintype "input"))
      (node (ref "R4") (pin "1") (pinfunction "1_1") (pintype "unspecified"))
      (node (ref "U12") (pin "14") (pinfunction "RTS#_14") (pintype "unspecified"))
    )
    (net (code "60") (name "SCS{slash}CMD") (class "Default")
      (node (ref "U6") (pin "30") (pinfunction "SD_CMD_30") (pintype "unspecified"))
      (node (ref "U8") (pin "1") (pinfunction "CS#_1") (pintype "unspecified"))
    )
    (net (code "61") (name "unconnected-(FPC1-Pad2)") (class "Default")
      (node (ref "FPC1") (pin "2") (pinfunction "2_2") (pintype "unspecified+no_connect"))
    )
    (net (code "62") (name "unconnected-(FPC2-Pad1)") (class "Default")
      (node (ref "FPC2") (pin "1") (pinfunction "1_1") (pintype "unspecified+no_connect"))
    )
    (net (code "63") (name "unconnected-(FPC2-Pad2)") (class "Default")
      (node (ref "FPC2") (pin "2") (pinfunction "2_2") (pintype "unspecified+no_connect"))
    )
    (net (code "64") (name "unconnected-(FPC2-Pad24)") (class "Default")
      (node (ref "FPC2") (pin "24") (pinfunction "24_24") (pintype "unspecified+no_connect"))
    )
    (net (code "65") (name "unconnected-(L2-GND-Pad4)") (class "Default")
      (node (ref "L2") (pin "4") (pinfunction "GND_4") (pintype "unspecified"))
    )
    (net (code "66") (name "unconnected-(SW4-Pad1)") (class "Default")
      (node (ref "SW4") (pin "1") (pinfunction "1_1") (pintype "unspecified+no_connect"))
    )
    (net (code "67") (name "unconnected-(U5-NC-Pad4)") (class "Default")
      (node (ref "U5") (pin "4") (pinfunction "NC_4") (pintype "unspecified+no_connect"))
    )
    (net (code "68") (name "unconnected-(U6-CAP1-Pad48)") (class "Default")
      (node (ref "U6") (pin "48") (pinfunction "CAP1_48") (pintype "unspecified+no_connect"))
    )
    (net (code "69") (name "unconnected-(U6-CAP2-Pad47)") (class "Default")
      (node (ref "U6") (pin "47") (pinfunction "CAP2_47") (pintype "unspecified+no_connect"))
    )
    (net (code "70") (name "unconnected-(U6-GPIO5-Pad34)") (class "Default")
      (node (ref "U6") (pin "34") (pinfunction "GPIO5_34") (pintype "unspecified+no_connect"))
    )
    (net (code "71") (name "unconnected-(U6-VDD_SDIO-Pad26)") (class "Default")
      (node (ref "U6") (pin "26") (pinfunction "VDD_SDIO_26") (pintype "unspecified+no_connect"))
    )
    (net (code "72") (name "unconnected-(U7-PPR-Pad2)") (class "Default")
      (node (ref "U7") (pin "2") (pinfunction "PPR_2") (pintype "unspecified"))
    )
    (net (code "73") (name "unconnected-(U11-Pad5)") (class "Default")
      (node (ref "U11") (pin "5") (pinfunction "5_5") (pintype "unspecified+no_connect"))
    )
    (net (code "74") (name "unconnected-(U12-CTS#-Pad9)") (class "Default")
      (node (ref "U12") (pin "9") (pinfunction "CTS#_9") (pintype "unspecified+no_connect"))
    )
    (net (code "75") (name "unconnected-(U12-DCD#-Pad12)") (class "Default")
      (node (ref "U12") (pin "12") (pinfunction "DCD#_12") (pintype "unspecified+no_connect"))
    )
    (net (code "76") (name "unconnected-(U12-DSR#-Pad10)") (class "Default")
      (node (ref "U12") (pin "10") (pinfunction "DSR#_10") (pintype "unspecified+no_connect"))
    )
    (net (code "77") (name "unconnected-(U12-NC.-Pad7)") (class "Default")
      (node (ref "U12") (pin "7") (pinfunction "NC._7") (pintype "unspecified+no_connect"))
    )
    (net (code "78") (name "unconnected-(U12-NC.-Pad8)") (class "Default")
      (node (ref "U12") (pin "8") (pinfunction "NC._8") (pintype "unspecified+no_connect"))
    )
    (net (code "79") (name "unconnected-(U12-R232-Pad15)") (class "Default")
      (node (ref "U12") (pin "15") (pinfunction "R232_15") (pintype "unspecified+no_connect"))
    )
    (net (code "80") (name "unconnected-(U12-RI#-Pad11)") (class "Default")
      (node (ref "U12") (pin "11") (pinfunction "RI#_11") (pintype "unspecified+no_connect"))
    )
    (net (code "81") (name "unconnected-(USB1-SBU1-PadA8)") (class "Default")
      (node (ref "USB1") (pin "A8") (pinfunction "SBU1_A8") (pintype "unspecified+no_connect"))
    )
    (net (code "82") (name "unconnected-(USB1-SBU2-PadB8)") (class "Default")
      (node (ref "USB1") (pin "B8") (pinfunction "SBU2_B8") (pintype "unspecified+no_connect"))
    )
  )
)
